# Stepper_board_dual_voltage_v2.net
KiCad netlist of a schematic drawn in EAGLE
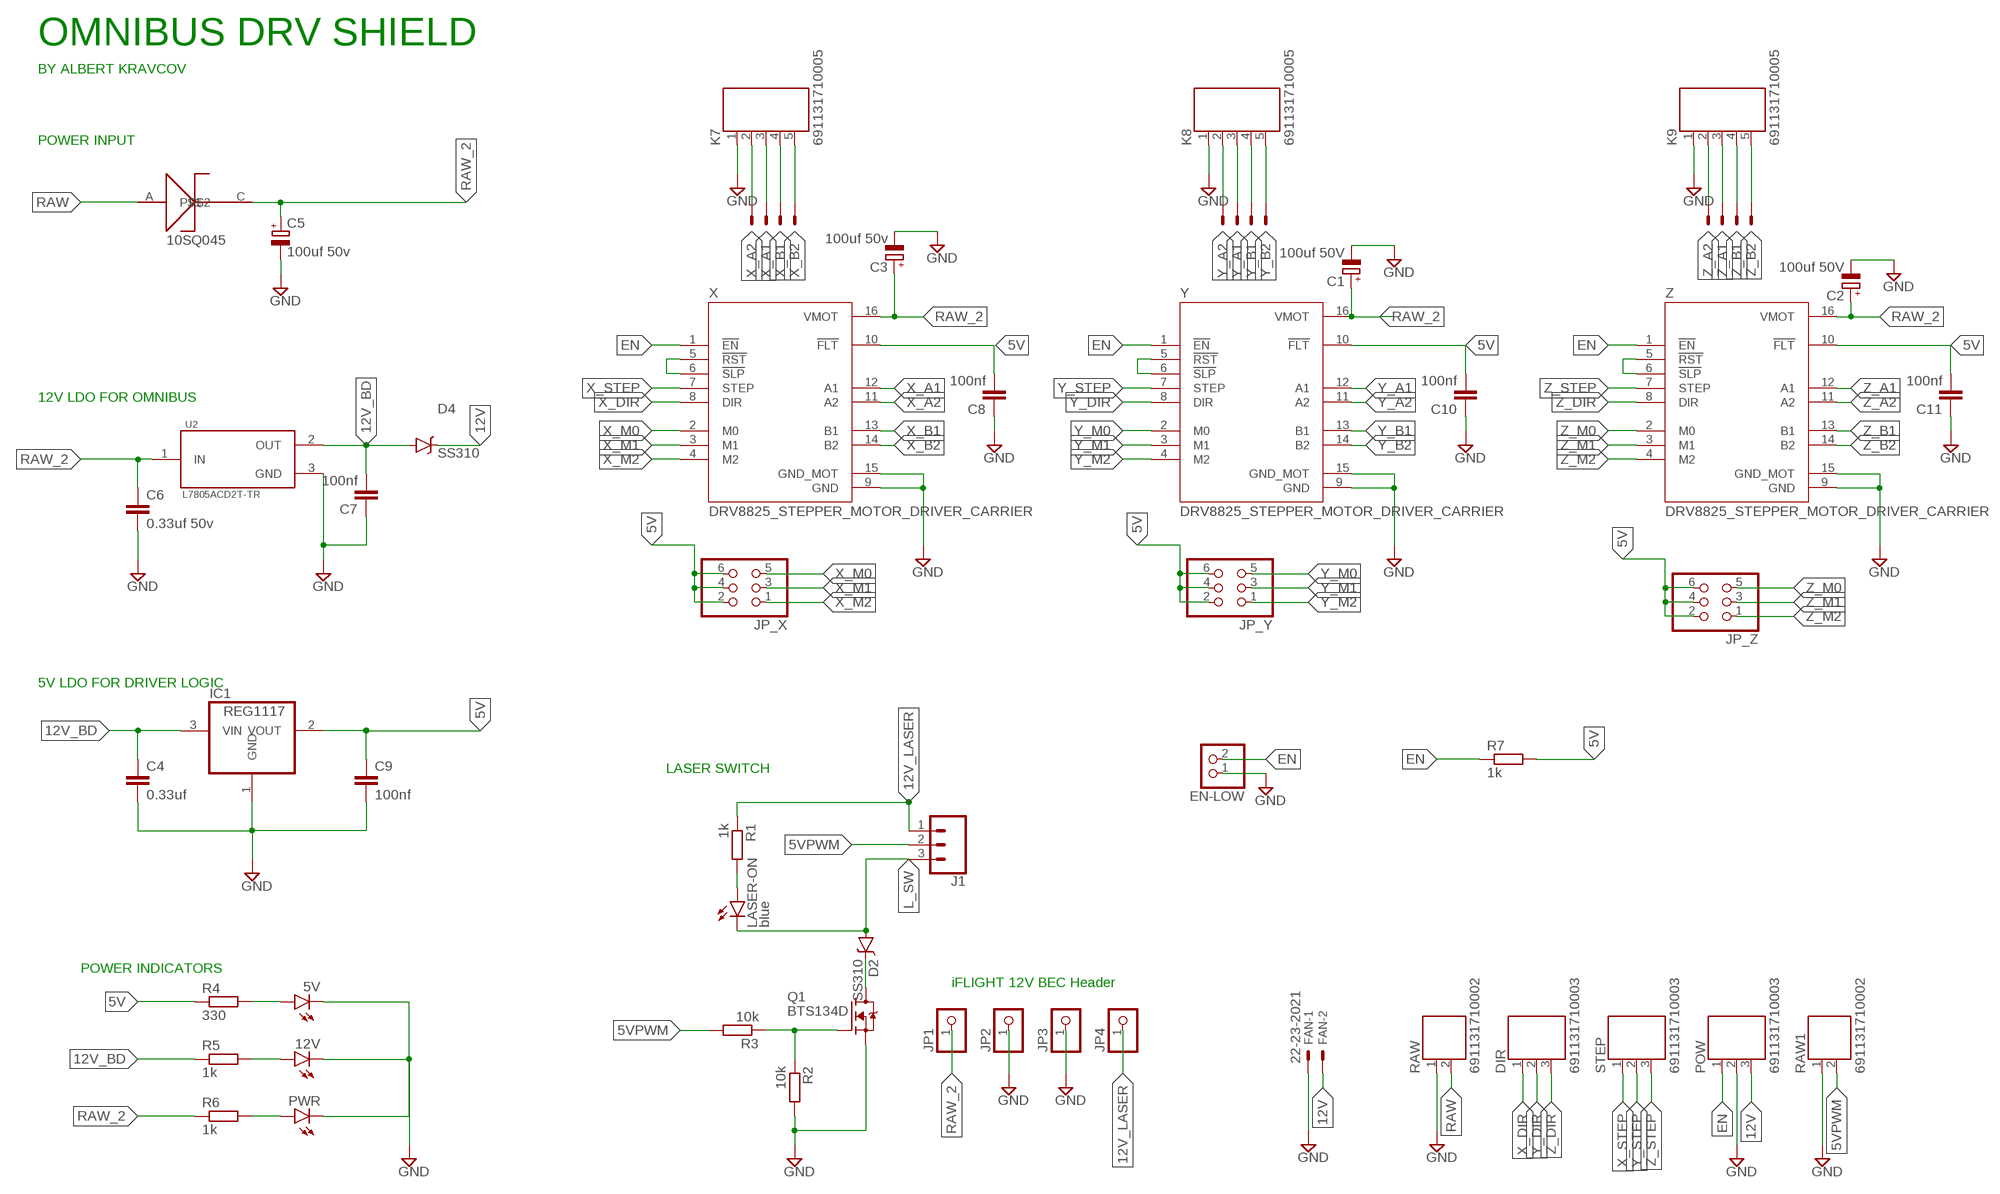
[diagram p0: schematic, sheet 1]

(export (version "E")
  (design (tool "Eeschema 10.0.6"))
  (components
    (comp (ref "5V")
      (value "LEDCHIPLED_0805")
      (footprint "eagle-import:CHIPLED_0805")
      (libsource (lib "eagle-import") (part "LEDCHIPLED_0805"))
    )
    (comp (ref "12V")
      (value "LEDCHIPLED_0805")
      (footprint "eagle-import:CHIPLED_0805")
      (libsource (lib "eagle-import") (part "LEDCHIPLED_0805"))
    )
    (comp (ref "C1")
      (value "100uf 50V")
      (footprint "eagle-import:E5-6")
      (libsource (lib "eagle-import") (part "CPOL-EUE5-6"))
    )
    (comp (ref "C2")
      (value "100uf 50V")
      (footprint "eagle-import:E5-6")
      (libsource (lib "eagle-import") (part "CPOL-EUE5-6"))
    )
    (comp (ref "C3")
      (value "100uf 50v")
      (footprint "eagle-import:E5-6")
      (libsource (lib "eagle-import") (part "CPOL-EUE5-6"))
    )
    (comp (ref "C4")
      (value "0.33uf")
      (footprint "eagle-import:C1206")
      (libsource (lib "eagle-import") (part "C-EUC1206"))
    )
    (comp (ref "C5")
      (value "100uf 50v")
      (footprint "eagle-import:E5-8,5")
      (libsource (lib "eagle-import") (part "rcl_334_CPOL-EUE5-8.5"))
    )
    (comp (ref "C6")
      (value "0.33uf 50v")
      (footprint "eagle-import:C1206")
      (libsource (lib "eagle-import") (part "C-EUC1206"))
    )
    (comp (ref "C7")
      (value "100nf")
      (footprint "eagle-import:C0805")
      (libsource (lib "eagle-import") (part "C-EUC0805"))
    )
    (comp (ref "C8")
      (value "100nf")
      (footprint "eagle-import:C0805")
      (libsource (lib "eagle-import") (part "C-EUC0805"))
    )
    (comp (ref "C9")
      (value "100nf")
      (footprint "eagle-import:C0805")
      (libsource (lib "eagle-import") (part "C-EUC0805"))
    )
    (comp (ref "C10")
      (value "100nf")
      (footprint "eagle-import:C0805")
      (libsource (lib "eagle-import") (part "C-EUC0805"))
    )
    (comp (ref "C11")
      (value "100nf")
      (footprint "eagle-import:C0805")
      (libsource (lib "eagle-import") (part "C-EUC0805"))
    )
    (comp (ref "D1")
      (value "10SQ045")
      (footprint "eagle-import:DIOAD885W125L910D885")
      (libsource (lib "eagle-import") (part "10SQ050"))
    )
    (comp (ref "D2")
      (value "SS310")
      (footprint "eagle-import:DO-214AC")
      (fields (field (name "MF") "Honeywell Sensing") (field (name "MP") "SS54"))
      (libsource (lib "eagle-import") (part "SS54"))
    )
    (comp (ref "D4")
      (value "SS310")
      (footprint "eagle-import:DO-214AC")
      (fields (field (name "MF") "Honeywell Sensing") (field (name "MP") "SS54"))
      (libsource (lib "eagle-import") (part "SS54"))
    )
    (comp (ref "DIR")
      (value "691131710003")
      (footprint "eagle-import:691131710003")
      (libsource (lib "eagle-import") (part "691131710003"))
    )
    (comp (ref "EN-LOW")
      (value "PINHD-1X2")
      (footprint "eagle-import:1X02")
      (libsource (lib "eagle-import") (part "PINHD-1X2"))
    )
    (comp (ref "FAN")
      (value "22-23-2021")
      (footprint "eagle-import:22-23-2021")
      (fields (field (name "MF") "MOLEX"))
      (libsource (lib "eagle-import") (part "22-23-2021"))
    )
    (comp (ref "IC1")
      (value "REG1117")
      (footprint "eagle-import:SOT223")
      (libsource (lib "eagle-import") (part "REG1117"))
    )
    (comp (ref "J1")
      (value "CONN_03")
      (footprint "eagle-import:1X03")
      (libsource (lib "eagle-import") (part "CONN_03"))
    )
    (comp (ref "JP1")
      (value "PINHD-1X1")
      (footprint "eagle-import:1X01")
      (libsource (lib "eagle-import") (part "PINHD-1X1"))
    )
    (comp (ref "JP2")
      (value "PINHD-1X1")
      (footprint "eagle-import:1X01")
      (libsource (lib "eagle-import") (part "PINHD-1X1"))
    )
    (comp (ref "JP3")
      (value "PINHD-1X1")
      (footprint "eagle-import:1X01")
      (libsource (lib "eagle-import") (part "PINHD-1X1"))
    )
    (comp (ref "JP4")
      (value "PINHD-1X1")
      (footprint "eagle-import:1X01")
      (libsource (lib "eagle-import") (part "PINHD-1X1"))
    )
    (comp (ref "JP_X")
      (value "PINHD-2X3")
      (footprint "eagle-import:2X03")
      (libsource (lib "eagle-import") (part "PINHD-2X3"))
    )
    (comp (ref "JP_Y")
      (value "PINHD-2X3")
      (footprint "eagle-import:2X03")
      (libsource (lib "eagle-import") (part "PINHD-2X3"))
    )
    (comp (ref "JP_Z")
      (value "PINHD-2X3")
      (footprint "eagle-import:2X03")
      (libsource (lib "eagle-import") (part "PINHD-2X3"))
    )
    (comp (ref "K7")
      (value "691131710005")
      (footprint "eagle-import:691131710005")
      (libsource (lib "eagle-import") (part "691131710005"))
    )
    (comp (ref "K8")
      (value "691131710005")
      (footprint "eagle-import:691131710005")
      (libsource (lib "eagle-import") (part "691131710005"))
    )
    (comp (ref "K9")
      (value "691131710005")
      (footprint "eagle-import:691131710005")
      (libsource (lib "eagle-import") (part "691131710005"))
    )
    (comp (ref "LASER-ON")
      (value "blue")
      (footprint "eagle-import:CHIPLED_0805")
      (libsource (lib "eagle-import") (part "LEDCHIPLED_0805"))
    )
    (comp (ref "POW")
      (value "691131710003")
      (footprint "eagle-import:691131710003")
      (libsource (lib "eagle-import") (part "691131710003"))
    )
    (comp (ref "PWR")
      (value "LEDCHIPLED_0805")
      (footprint "eagle-import:CHIPLED_0805")
      (libsource (lib "eagle-import") (part "LEDCHIPLED_0805"))
    )
    (comp (ref "Q1")
      (value "BTS134D")
      (footprint "eagle-import:TO-252")
      (fields (field (name "MF") "ON Semiconductor") (field (name "MP") "FQD7N10LTM"))
      (libsource (lib "eagle-import") (part "FQD7N10LTM"))
    )
    (comp (ref "R1")
      (value "1k")
      (footprint "eagle-import:R0805")
      (libsource (lib "eagle-import") (part "R-EU_R0805"))
    )
    (comp (ref "R2")
      (value "10k")
      (footprint "eagle-import:R0805")
      (libsource (lib "eagle-import") (part "R-EU_R0805"))
    )
    (comp (ref "R3")
      (value "10k")
      (footprint "eagle-import:R0805")
      (libsource (lib "eagle-import") (part "R-EU_R0805"))
    )
    (comp (ref "R4")
      (value "330")
      (footprint "eagle-import:R0805")
      (libsource (lib "eagle-import") (part "R-EU_R0805"))
    )
    (comp (ref "R5")
      (value "1k")
      (footprint "eagle-import:R0805")
      (libsource (lib "eagle-import") (part "R-EU_R0805"))
    )
    (comp (ref "R6")
      (value "1k")
      (footprint "eagle-import:R1206")
      (libsource (lib "eagle-import") (part "R-EU_R1206"))
    )
    (comp (ref "R7")
      (value "1k")
      (footprint "eagle-import:R0805")
      (libsource (lib "eagle-import") (part "R-EU_R0805"))
    )
    (comp (ref "RAW")
      (value "691131710002")
      (footprint "eagle-import:691131710002")
      (libsource (lib "eagle-import") (part "691131710002"))
    )
    (comp (ref "RAW1")
      (value "691131710002")
      (footprint "eagle-import:691131710002")
      (libsource (lib "eagle-import") (part "691131710002"))
    )
    (comp (ref "STEP")
      (value "691131710003")
      (footprint "eagle-import:691131710003")
      (libsource (lib "eagle-import") (part "691131710003"))
    )
    (comp (ref "U2")
      (value "L7805ACD2T-TR")
      (footprint "eagle-import:TO254P1515X470-3N")
      (fields (field (name "MF") "STMicroelectronics"))
      (libsource (lib "eagle-import") (part "L7805ACD2T-TR"))
    )
    (comp (ref "X")
      (value "DRV8825_STEPPER_MOTOR_DRIVER_CARRIER")
      (footprint "eagle-import:IC_DRV8825_STEPPER_MOTOR_DRIVER_CARRIER")
      (fields (field (name "MF") "Pololu") (field (name "MP") "DRV8825 STEPPER MOTOR DRIVER CARRIER"))
      (libsource (lib "eagle-import") (part "DRV8825_STEPPER_MOTOR_DRIVER_CARRIER"))
    )
    (comp (ref "X_MOTOR")
      (value "22-23-2041")
      (footprint "eagle-import:22-23-2041")
      (fields (field (name "MF") "MOLEX"))
      (libsource (lib "eagle-import") (part "22-23-2041"))
    )
    (comp (ref "Y")
      (value "DRV8825_STEPPER_MOTOR_DRIVER_CARRIER")
      (footprint "eagle-import:IC_DRV8825_STEPPER_MOTOR_DRIVER_CARRIER")
      (fields (field (name "MF") "Pololu") (field (name "MP") "DRV8825 STEPPER MOTOR DRIVER CARRIER"))
      (libsource (lib "eagle-import") (part "DRV8825_STEPPER_MOTOR_DRIVER_CARRIER"))
    )
    (comp (ref "Y_MOTOR")
      (value "22-23-2041")
      (footprint "eagle-import:22-23-2041")
      (fields (field (name "MF") "MOLEX"))
      (libsource (lib "eagle-import") (part "22-23-2041"))
    )
    (comp (ref "Z")
      (value "DRV8825_STEPPER_MOTOR_DRIVER_CARRIER")
      (footprint "eagle-import:IC_DRV8825_STEPPER_MOTOR_DRIVER_CARRIER")
      (fields (field (name "MF") "Pololu") (field (name "MP") "DRV8825 STEPPER MOTOR DRIVER CARRIER"))
      (libsource (lib "eagle-import") (part "DRV8825_STEPPER_MOTOR_DRIVER_CARRIER"))
    )
    (comp (ref "Z_MOTOR")
      (value "22-23-2041")
      (footprint "eagle-import:22-23-2041")
      (fields (field (name "MF") "MOLEX"))
      (libsource (lib "eagle-import") (part "22-23-2041"))
    )
  )
  (nets
    (net (code "1") (name "5V") (class "Default")
      (node (ref "C10") (pin "2") (pinfunction "2_2") (pintype "passive"))
      (node (ref "C11") (pin "2") (pinfunction "2_2") (pintype "passive"))
      (node (ref "C8") (pin "2") (pinfunction "2_2") (pintype "passive"))
      (node (ref "C9") (pin "1") (pinfunction "1_1") (pintype "passive"))
      (node (ref "IC1") (pin "2") (pinfunction "VOUT_2") (pintype "output"))
      (node (ref "JP_X") (pin "2") (pinfunction "2_2") (pintype "passive"))
      (node (ref "JP_X") (pin "4") (pinfunction "4_4") (pintype "passive"))
      (node (ref "JP_X") (pin "6") (pinfunction "6_6") (pintype "passive"))
      (node (ref "JP_Y") (pin "2") (pinfunction "2_2") (pintype "passive"))
      (node (ref "JP_Y") (pin "4") (pinfunction "4_4") (pintype "passive"))
      (node (ref "JP_Y") (pin "6") (pinfunction "6_6") (pintype "passive"))
      (node (ref "JP_Z") (pin "2") (pinfunction "2_2") (pintype "passive"))
      (node (ref "JP_Z") (pin "4") (pinfunction "4_4") (pintype "passive"))
      (node (ref "JP_Z") (pin "6") (pinfunction "6_6") (pintype "passive"))
      (node (ref "R4") (pin "1") (pinfunction "1_1") (pintype "passive"))
      (node (ref "R7") (pin "2") (pinfunction "2_2") (pintype "passive"))
      (node (ref "X") (pin "10") (pinfunction "~{FLT}_10") (pintype "output"))
      (node (ref "Y") (pin "10") (pinfunction "~{FLT}_10") (pintype "output"))
      (node (ref "Z") (pin "10") (pinfunction "~{FLT}_10") (pintype "output"))
    )
    (net (code "2") (name "5VPWM") (class "Default")
      (node (ref "J1") (pin "2") (pinfunction "2_2") (pintype "passive"))
      (node (ref "R3") (pin "2") (pinfunction "2_2") (pintype "passive"))
      (node (ref "RAW1") (pin "2") (pinfunction "2_2") (pintype "passive"))
    )
    (net (code "3") (name "12V") (class "Default")
      (node (ref "D4") (pin "C") (pinfunction "C_C") (pintype "passive"))
      (node (ref "FAN") (pin "2") (pinfunction "S_2") (pintype "passive"))
      (node (ref "POW") (pin "3") (pinfunction "3_3") (pintype "passive"))
    )
    (net (code "4") (name "12V_BD") (class "Default")
      (node (ref "C4") (pin "1") (pinfunction "1_1") (pintype "passive"))
      (node (ref "C7") (pin "2") (pinfunction "2_2") (pintype "passive"))
      (node (ref "D4") (pin "A") (pinfunction "A_A") (pintype "passive"))
      (node (ref "IC1") (pin "3") (pinfunction "VIN_3") (pintype "input"))
      (node (ref "R5") (pin "1") (pinfunction "1_1") (pintype "passive"))
      (node (ref "U2") (pin "2") (pinfunction "OUT_2") (pintype "output"))
    )
    (net (code "5") (name "12V_LASER") (class "Default")
      (node (ref "J1") (pin "1") (pinfunction "1_1") (pintype "passive"))
      (node (ref "JP4") (pin "1") (pinfunction "1_1") (pintype "passive"))
      (node (ref "R1") (pin "1") (pinfunction "1_1") (pintype "passive"))
    )
    (net (code "6") (name "EN") (class "Default")
      (node (ref "EN-LOW") (pin "2") (pinfunction "2_2") (pintype "passive"))
      (node (ref "POW") (pin "1") (pinfunction "1_1") (pintype "passive"))
      (node (ref "R7") (pin "1") (pinfunction "1_1") (pintype "passive"))
      (node (ref "X") (pin "1") (pinfunction "~{EN}_1") (pintype "input"))
      (node (ref "Y") (pin "1") (pinfunction "~{EN}_1") (pintype "input"))
      (node (ref "Z") (pin "1") (pinfunction "~{EN}_1") (pintype "input"))
    )
    (net (code "7") (name "GND") (class "Default")
      (node (ref "12V") (pin "C") (pinfunction "C_C") (pintype "passive"))
      (node (ref "5V") (pin "C") (pinfunction "C_C") (pintype "passive"))
      (node (ref "C1") (pin "-") (pinfunction "-_-") (pintype "passive"))
      (node (ref "C10") (pin "1") (pinfunction "1_1") (pintype "passive"))
      (node (ref "C11") (pin "1") (pinfunction "1_1") (pintype "passive"))
      (node (ref "C2") (pin "-") (pinfunction "-_-") (pintype "passive"))
      (node (ref "C3") (pin "-") (pinfunction "-_-") (pintype "passive"))
      (node (ref "C4") (pin "2") (pinfunction "2_2") (pintype "passive"))
      (node (ref "C5") (pin "-") (pinfunction "-_-") (pintype "passive"))
      (node (ref "C6") (pin "2") (pinfunction "2_2") (pintype "passive"))
      (node (ref "C7") (pin "1") (pinfunction "1_1") (pintype "passive"))
      (node (ref "C8") (pin "1") (pinfunction "1_1") (pintype "passive"))
      (node (ref "C9") (pin "2") (pinfunction "2_2") (pintype "passive"))
      (node (ref "EN-LOW") (pin "1") (pinfunction "1_1") (pintype "passive"))
      (node (ref "FAN") (pin "1") (pinfunction "S_1") (pintype "passive"))
      (node (ref "IC1") (pin "1") (pinfunction "GND_1") (pintype "power_in"))
      (node (ref "JP2") (pin "1") (pinfunction "1_1") (pintype "passive"))
      (node (ref "JP3") (pin "1") (pinfunction "1_1") (pintype "passive"))
      (node (ref "K7") (pin "1") (pinfunction "1_1") (pintype "passive"))
      (node (ref "K8") (pin "1") (pinfunction "1_1") (pintype "passive"))
      (node (ref "K9") (pin "1") (pinfunction "1_1") (pintype "passive"))
      (node (ref "POW") (pin "2") (pinfunction "2_2") (pintype "passive"))
      (node (ref "PWR") (pin "C") (pinfunction "C_C") (pintype "passive"))
      (node (ref "Q1") (pin "3") (pinfunction "S_3") (pintype "passive"))
      (node (ref "R2") (pin "2") (pinfunction "2_2") (pintype "passive"))
      (node (ref "RAW") (pin "1") (pinfunction "1_1") (pintype "passive"))
      (node (ref "RAW1") (pin "1") (pinfunction "1_1") (pintype "passive"))
      (node (ref "U2") (pin "3") (pinfunction "GND_3") (pintype "power_in"))
      (node (ref "X") (pin "15") (pinfunction "GND_MOT_15") (pintype "power_in"))
      (node (ref "X") (pin "9") (pinfunction "GND_9") (pintype "power_in"))
      (node (ref "Y") (pin "15") (pinfunction "GND_MOT_15") (pintype "power_in"))
      (node (ref "Y") (pin "9") (pinfunction "GND_9") (pintype "power_in"))
      (node (ref "Z") (pin "15") (pinfunction "GND_MOT_15") (pintype "power_in"))
      (node (ref "Z") (pin "9") (pinfunction "GND_9") (pintype "power_in"))
    )
    (net (code "8") (name "L_SW") (class "Default")
      (node (ref "D2") (pin "A") (pinfunction "A_A") (pintype "passive"))
      (node (ref "J1") (pin "3") (pinfunction "3_3") (pintype "passive"))
      (node (ref "LASER-ON") (pin "C") (pinfunction "C_C") (pintype "passive"))
    )
    (net (code "9") (name "Net-(5V-PadA)") (class "Default")
      (node (ref "5V") (pin "A") (pinfunction "A_A") (pintype "passive"))
      (node (ref "R4") (pin "2") (pinfunction "2_2") (pintype "passive"))
    )
    (net (code "10") (name "Net-(12V-PadA)") (class "Default")
      (node (ref "12V") (pin "A") (pinfunction "A_A") (pintype "passive"))
      (node (ref "R5") (pin "2") (pinfunction "2_2") (pintype "passive"))
    )
    (net (code "11") (name "Net-(LASER-ON-PadA)") (class "Default")
      (node (ref "LASER-ON") (pin "A") (pinfunction "A_A") (pintype "passive"))
      (node (ref "R1") (pin "2") (pinfunction "2_2") (pintype "passive"))
    )
    (net (code "12") (name "Net-(PWR-PadA)") (class "Default")
      (node (ref "PWR") (pin "A") (pinfunction "A_A") (pintype "passive"))
      (node (ref "R6") (pin "2") (pinfunction "2_2") (pintype "passive"))
    )
    (net (code "13") (name "Net-(Q1-D)") (class "Default")
      (node (ref "D2") (pin "C") (pinfunction "C_C") (pintype "passive"))
      (node (ref "Q1") (pin "T") (pinfunction "D_T") (pintype "passive"))
    )
    (net (code "14") (name "Net-(Q1-G)") (class "Default")
      (node (ref "Q1") (pin "1") (pinfunction "G_1") (pintype "passive"))
      (node (ref "R2") (pin "1") (pinfunction "1_1") (pintype "passive"))
      (node (ref "R3") (pin "1") (pinfunction "1_1") (pintype "passive"))
    )
    (net (code "15") (name "Net-(X-~{RST})") (class "Default")
      (node (ref "X") (pin "5") (pinfunction "~{RST}_5") (pintype "input"))
      (node (ref "X") (pin "6") (pinfunction "~{SLP}_6") (pintype "input"))
    )
    (net (code "16") (name "Net-(Y-~{RST})") (class "Default")
      (node (ref "Y") (pin "5") (pinfunction "~{RST}_5") (pintype "input"))
      (node (ref "Y") (pin "6") (pinfunction "~{SLP}_6") (pintype "input"))
    )
    (net (code "17") (name "Net-(Z-~{RST})") (class "Default")
      (node (ref "Z") (pin "5") (pinfunction "~{RST}_5") (pintype "input"))
      (node (ref "Z") (pin "6") (pinfunction "~{SLP}_6") (pintype "input"))
    )
    (net (code "18") (name "RAW") (class "Default")
      (node (ref "D1") (pin "A") (pinfunction "P$1_A") (pintype "bidirectional"))
      (node (ref "RAW") (pin "2") (pinfunction "2_2") (pintype "passive"))
    )
    (net (code "19") (name "RAW_2") (class "Default")
      (node (ref "C1") (pin "+") (pinfunction "+_+") (pintype "passive"))
      (node (ref "C2") (pin "+") (pinfunction "+_+") (pintype "passive"))
      (node (ref "C3") (pin "+") (pinfunction "+_+") (pintype "passive"))
      (node (ref "C5") (pin "+") (pinfunction "+_+") (pintype "passive"))
      (node (ref "C6") (pin "1") (pinfunction "1_1") (pintype "passive"))
      (node (ref "D1") (pin "C") (pinfunction "P$2_C") (pintype "bidirectional"))
      (node (ref "JP1") (pin "1") (pinfunction "1_1") (pintype "passive"))
      (node (ref "R6") (pin "1") (pinfunction "1_1") (pintype "passive"))
      (node (ref "U2") (pin "1") (pinfunction "IN_1") (pintype "input"))
      (node (ref "X") (pin "16") (pinfunction "VMOT_16") (pintype "power_in"))
      (node (ref "Y") (pin "16") (pinfunction "VMOT_16") (pintype "power_in"))
      (node (ref "Z") (pin "16") (pinfunction "VMOT_16") (pintype "power_in"))
    )
    (net (code "20") (name "X_A1") (class "Default")
      (node (ref "K7") (pin "3") (pinfunction "3_3") (pintype "passive"))
      (node (ref "X") (pin "12") (pinfunction "A1_12") (pintype "output"))
      (node (ref "X_MOTOR") (pin "3") (pinfunction "S_3") (pintype "passive"))
    )
    (net (code "21") (name "X_A2") (class "Default")
      (node (ref "K7") (pin "2") (pinfunction "2_2") (pintype "passive"))
      (node (ref "X") (pin "11") (pinfunction "A2_11") (pintype "output"))
      (node (ref "X_MOTOR") (pin "4") (pinfunction "S_4") (pintype "passive"))
    )
    (net (code "22") (name "X_B1") (class "Default")
      (node (ref "K7") (pin "4") (pinfunction "4_4") (pintype "passive"))
      (node (ref "X") (pin "13") (pinfunction "B1_13") (pintype "output"))
      (node (ref "X_MOTOR") (pin "2") (pinfunction "S_2") (pintype "passive"))
    )
    (net (code "23") (name "X_B2") (class "Default")
      (node (ref "K7") (pin "5") (pinfunction "5_5") (pintype "passive"))
      (node (ref "X") (pin "14") (pinfunction "B2_14") (pintype "output"))
      (node (ref "X_MOTOR") (pin "1") (pinfunction "S_1") (pintype "passive"))
    )
    (net (code "24") (name "X_DIR") (class "Default")
      (node (ref "DIR") (pin "1") (pinfunction "1_1") (pintype "passive"))
      (node (ref "X") (pin "8") (pinfunction "DIR_8") (pintype "input"))
    )
    (net (code "25") (name "X_M0") (class "Default")
      (node (ref "JP_X") (pin "5") (pinfunction "5_5") (pintype "passive"))
      (node (ref "X") (pin "2") (pinfunction "M0_2") (pintype "input"))
    )
    (net (code "26") (name "X_M1") (class "Default")
      (node (ref "JP_X") (pin "3") (pinfunction "3_3") (pintype "passive"))
      (node (ref "X") (pin "3") (pinfunction "M1_3") (pintype "input"))
    )
    (net (code "27") (name "X_M2") (class "Default")
      (node (ref "JP_X") (pin "1") (pinfunction "1_1") (pintype "passive"))
      (node (ref "X") (pin "4") (pinfunction "M2_4") (pintype "input"))
    )
    (net (code "28") (name "X_STEP") (class "Default")
      (node (ref "STEP") (pin "1") (pinfunction "1_1") (pintype "passive"))
      (node (ref "X") (pin "7") (pinfunction "STEP_7") (pintype "input"))
    )
    (net (code "29") (name "Y_A1") (class "Default")
      (node (ref "K8") (pin "3") (pinfunction "3_3") (pintype "passive"))
      (node (ref "Y") (pin "12") (pinfunction "A1_12") (pintype "output"))
      (node (ref "Y_MOTOR") (pin "3") (pinfunction "S_3") (pintype "passive"))
    )
    (net (code "30") (name "Y_A2") (class "Default")
      (node (ref "K8") (pin "2") (pinfunction "2_2") (pintype "passive"))
      (node (ref "Y") (pin "11") (pinfunction "A2_11") (pintype "output"))
      (node (ref "Y_MOTOR") (pin "4") (pinfunction "S_4") (pintype "passive"))
    )
    (net (code "31") (name "Y_B1") (class "Default")
      (node (ref "K8") (pin "4") (pinfunction "4_4") (pintype "passive"))
      (node (ref "Y") (pin "13") (pinfunction "B1_13") (pintype "output"))
      (node (ref "Y_MOTOR") (pin "2") (pinfunction "S_2") (pintype "passive"))
    )
    (net (code "32") (name "Y_B2") (class "Default")
      (node (ref "K8") (pin "5") (pinfunction "5_5") (pintype "passive"))
      (node (ref "Y") (pin "14") (pinfunction "B2_14") (pintype "output"))
      (node (ref "Y_MOTOR") (pin "1") (pinfunction "S_1") (pintype "passive"))
    )
    (net (code "33") (name "Y_DIR") (class "Default")
      (node (ref "DIR") (pin "2") (pinfunction "2_2") (pintype "passive"))
      (node (ref "Y") (pin "8") (pinfunction "DIR_8") (pintype "input"))
    )
    (net (code "34") (name "Y_M0") (class "Default")
      (node (ref "JP_Y") (pin "5") (pinfunction "5_5") (pintype "passive"))
      (node (ref "Y") (pin "2") (pinfunction "M0_2") (pintype "input"))
    )
    (net (code "35") (name "Y_M1") (class "Default")
      (node (ref "JP_Y") (pin "3") (pinfunction "3_3") (pintype "passive"))
      (node (ref "Y") (pin "3") (pinfunction "M1_3") (pintype "input"))
    )
    (net (code "36") (name "Y_M2") (class "Default")
      (node (ref "JP_Y") (pin "1") (pinfunction "1_1") (pintype "passive"))
      (node (ref "Y") (pin "4") (pinfunction "M2_4") (pintype "input"))
    )
    (net (code "37") (name "Y_STEP") (class "Default")
      (node (ref "STEP") (pin "2") (pinfunction "2_2") (pintype "passive"))
      (node (ref "Y") (pin "7") (pinfunction "STEP_7") (pintype "input"))
    )
    (net (code "38") (name "Z_A1") (class "Default")
      (node (ref "K9") (pin "3") (pinfunction "3_3") (pintype "passive"))
      (node (ref "Z") (pin "12") (pinfunction "A1_12") (pintype "output"))
      (node (ref "Z_MOTOR") (pin "3") (pinfunction "S_3") (pintype "passive"))
    )
    (net (code "39") (name "Z_A2") (class "Default")
      (node (ref "K9") (pin "2") (pinfunction "2_2") (pintype "passive"))
      (node (ref "Z") (pin "11") (pinfunction "A2_11") (pintype "output"))
      (node (ref "Z_MOTOR") (pin "4") (pinfunction "S_4") (pintype "passive"))
    )
    (net (code "40") (name "Z_B1") (class "Default")
      (node (ref "K9") (pin "4") (pinfunction "4_4") (pintype "passive"))
      (node (ref "Z") (pin "13") (pinfunction "B1_13") (pintype "output"))
      (node (ref "Z_MOTOR") (pin "2") (pinfunction "S_2") (pintype "passive"))
    )
    (net (code "41") (name "Z_B2") (class "Default")
      (node (ref "K9") (pin "5") (pinfunction "5_5") (pintype "passive"))
      (node (ref "Z") (pin "14") (pinfunction "B2_14") (pintype "output"))
      (node (ref "Z_MOTOR") (pin "1") (pinfunction "S_1") (pintype "passive"))
    )
    (net (code "42") (name "Z_DIR") (class "Default")
      (node (ref "DIR") (pin "3") (pinfunction "3_3") (pintype "passive"))
      (node (ref "Z") (pin "8") (pinfunction "DIR_8") (pintype "input"))
    )
    (net (code "43") (name "Z_M0") (class "Default")
      (node (ref "JP_Z") (pin "5") (pinfunction "5_5") (pintype "passive"))
      (node (ref "Z") (pin "2") (pinfunction "M0_2") (pintype "input"))
    )
    (net (code "44") (name "Z_M1") (class "Default")
      (node (ref "JP_Z") (pin "3") (pinfunction "3_3") (pintype "passive"))
      (node (ref "Z") (pin "3") (pinfunction "M1_3") (pintype "input"))
    )
    (net (code "45") (name "Z_M2") (class "Default")
      (node (ref "JP_Z") (pin "1") (pinfunction "1_1") (pintype "passive"))
      (node (ref "Z") (pin "4") (pinfunction "M2_4") (pintype "input"))
    )
    (net (code "46") (name "Z_STEP") (class "Default")
      (node (ref "STEP") (pin "3") (pinfunction "3_3") (pintype "passive"))
      (node (ref "Z") (pin "7") (pinfunction "STEP_7") (pintype "input"))
    )
  )
)
